# FirstProject.net
KiCad netlist of a schematic drawn in Altium Designer
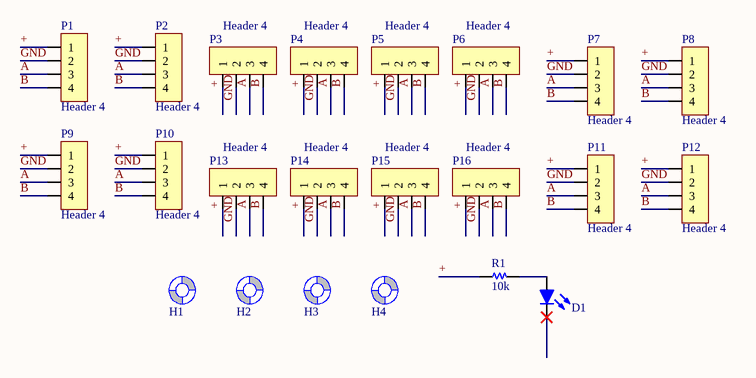
[diagram p0: FirstProject.SchDoc]

(export (version "E")
  (design (tool "Eeschema 10.0.6"))
  (components
    (comp (ref "D1")
      (value "Led")
      (footprint "Led 0603 - red")
      (description "Typical LED")
      (libsource (lib "led") (part "Led"))
    )
    (comp (ref "H1")
      (value "Screw Hole")
      (footprint "SCREW/3.0/6.0")
      (libsource (lib "chipfc_libs") (part "Screw Hole"))
    )
    (comp (ref "H2")
      (value "Screw Hole")
      (footprint "SCREW/3.0/6.0")
      (libsource (lib "chipfc_libs") (part "Screw Hole"))
    )
    (comp (ref "H3")
      (value "Screw Hole")
      (footprint "SCREW/3.0/6.0")
      (libsource (lib "chipfc_libs") (part "Screw Hole"))
    )
    (comp (ref "H4")
      (value "Screw Hole")
      (footprint "SCREW/3.0/6.0")
      (libsource (lib "chipfc_libs") (part "Screw Hole"))
    )
    (comp (ref "P1")
      (value "Header 4")
      (footprint "HDR/Header/4/BOX")
      (description "Header, 4-Pin")
      (libsource (lib "") (part "Header 4_1"))
    )
    (comp (ref "P2")
      (value "Header 4")
      (footprint "HDR/Header/4/BOX")
      (description "Header, 4-Pin")
      (libsource (lib "") (part "Header 4_1"))
    )
    (comp (ref "P3")
      (value "Header 4")
      (footprint "HDR/Terminal/4/RA")
      (description "Header, 4-Pin")
      (libsource (lib "connectors") (part "Header 4"))
    )
    (comp (ref "P4")
      (value "Header 4")
      (footprint "HDR/Terminal/4/RA")
      (description "Header, 4-Pin")
      (libsource (lib "connectors") (part "Header 4"))
    )
    (comp (ref "P5")
      (value "Header 4")
      (footprint "HDR/Terminal/4/RA")
      (description "Header, 4-Pin")
      (libsource (lib "connectors") (part "Header 4"))
    )
    (comp (ref "P6")
      (value "Header 4")
      (footprint "HDR/Terminal/4/RA")
      (description "Header, 4-Pin")
      (libsource (lib "connectors") (part "Header 4"))
    )
    (comp (ref "P7")
      (value "Header 4")
      (footprint "HDR/Header/4/BOX")
      (description "Header, 4-Pin")
      (libsource (lib "") (part "Header 4_1"))
    )
    (comp (ref "P8")
      (value "Header 4")
      (footprint "HDR/Header/4/BOX")
      (description "Header, 4-Pin")
      (libsource (lib "") (part "Header 4_1"))
    )
    (comp (ref "P9")
      (value "Header 4")
      (footprint "HDR/Header/4/BOX")
      (description "Header, 4-Pin")
      (libsource (lib "") (part "Header 4_1"))
    )
    (comp (ref "P10")
      (value "Header 4")
      (footprint "HDR/Header/4/BOX")
      (description "Header, 4-Pin")
      (libsource (lib "") (part "Header 4_1"))
    )
    (comp (ref "P11")
      (value "Header 4")
      (footprint "HDR/Header/4/BOX")
      (description "Header, 4-Pin")
      (libsource (lib "") (part "Header 4_1"))
    )
    (comp (ref "P12")
      (value "Header 4")
      (footprint "HDR/Header/4/BOX")
      (description "Header, 4-Pin")
      (libsource (lib "") (part "Header 4_1"))
    )
    (comp (ref "P13")
      (value "Header 4")
      (footprint "HDR/Terminal/4/RA")
      (description "Header, 4-Pin")
      (libsource (lib "connectors") (part "Header 4"))
    )
    (comp (ref "P14")
      (value "Header 4")
      (footprint "HDR/Terminal/4/RA")
      (description "Header, 4-Pin")
      (libsource (lib "connectors") (part "Header 4"))
    )
    (comp (ref "P15")
      (value "Header 4")
      (footprint "HDR/Terminal/4/RA")
      (description "Header, 4-Pin")
      (libsource (lib "connectors") (part "Header 4"))
    )
    (comp (ref "P16")
      (value "Header 4")
      (footprint "HDR/Terminal/4/RA")
      (description "Header, 4-Pin")
      (libsource (lib "connectors") (part "Header 4"))
    )
    (comp (ref "R1")
      (value "10k")
      (footprint "R 0805")
      (description "Resistor")
      (libsource (lib "chipfc_libs") (part "Resistor"))
    )
  )
  (nets
    (net (code "1") (name "/+") (class "Default")
      (node (ref "P1") (pin "1") (pinfunction "1_1") (pintype "passive"))
      (node (ref "P10") (pin "1") (pinfunction "1_1") (pintype "passive"))
      (node (ref "P11") (pin "1") (pinfunction "1_1") (pintype "passive"))
      (node (ref "P12") (pin "1") (pinfunction "1_1") (pintype "passive"))
      (node (ref "P13") (pin "1") (pinfunction "1_1") (pintype "passive"))
      (node (ref "P14") (pin "1") (pinfunction "1_1") (pintype "passive"))
      (node (ref "P15") (pin "1") (pinfunction "1_1") (pintype "passive"))
      (node (ref "P16") (pin "1") (pinfunction "1_1") (pintype "passive"))
      (node (ref "P2") (pin "1") (pinfunction "1_1") (pintype "passive"))
      (node (ref "P3") (pin "1") (pinfunction "1_1") (pintype "passive"))
      (node (ref "P4") (pin "1") (pinfunction "1_1") (pintype "passive"))
      (node (ref "P5") (pin "1") (pinfunction "1_1") (pintype "passive"))
      (node (ref "P6") (pin "1") (pinfunction "1_1") (pintype "passive"))
      (node (ref "P7") (pin "1") (pinfunction "1_1") (pintype "passive"))
      (node (ref "P8") (pin "1") (pinfunction "1_1") (pintype "passive"))
      (node (ref "P9") (pin "1") (pinfunction "1_1") (pintype "passive"))
      (node (ref "R1") (pin "1") (pinfunction "1_1") (pintype "passive"))
    )
    (net (code "2") (name "/A") (class "Default")
      (node (ref "P1") (pin "3") (pinfunction "3_3") (pintype "passive"))
      (node (ref "P10") (pin "3") (pinfunction "3_3") (pintype "passive"))
      (node (ref "P11") (pin "3") (pinfunction "3_3") (pintype "passive"))
      (node (ref "P12") (pin "3") (pinfunction "3_3") (pintype "passive"))
      (node (ref "P13") (pin "3") (pinfunction "3_3") (pintype "passive"))
      (node (ref "P14") (pin "3") (pinfunction "3_3") (pintype "passive"))
      (node (ref "P15") (pin "3") (pinfunction "3_3") (pintype "passive"))
      (node (ref "P16") (pin "3") (pinfunction "3_3") (pintype "passive"))
      (node (ref "P2") (pin "3") (pinfunction "3_3") (pintype "passive"))
      (node (ref "P3") (pin "3") (pinfunction "3_3") (pintype "passive"))
      (node (ref "P4") (pin "3") (pinfunction "3_3") (pintype "passive"))
      (node (ref "P5") (pin "3") (pinfunction "3_3") (pintype "passive"))
      (node (ref "P6") (pin "3") (pinfunction "3_3") (pintype "passive"))
      (node (ref "P7") (pin "3") (pinfunction "3_3") (pintype "passive"))
      (node (ref "P8") (pin "3") (pinfunction "3_3") (pintype "passive"))
      (node (ref "P9") (pin "3") (pinfunction "3_3") (pintype "passive"))
    )
    (net (code "3") (name "/B") (class "Default")
      (node (ref "P1") (pin "4") (pinfunction "4_4") (pintype "passive"))
      (node (ref "P10") (pin "4") (pinfunction "4_4") (pintype "passive"))
      (node (ref "P11") (pin "4") (pinfunction "4_4") (pintype "passive"))
      (node (ref "P12") (pin "4") (pinfunction "4_4") (pintype "passive"))
      (node (ref "P13") (pin "4") (pinfunction "4_4") (pintype "passive"))
      (node (ref "P14") (pin "4") (pinfunction "4_4") (pintype "passive"))
      (node (ref "P15") (pin "4") (pinfunction "4_4") (pintype "passive"))
      (node (ref "P16") (pin "4") (pinfunction "4_4") (pintype "passive"))
      (node (ref "P2") (pin "4") (pinfunction "4_4") (pintype "passive"))
      (node (ref "P3") (pin "4") (pinfunction "4_4") (pintype "passive"))
      (node (ref "P4") (pin "4") (pinfunction "4_4") (pintype "passive"))
      (node (ref "P5") (pin "4") (pinfunction "4_4") (pintype "passive"))
      (node (ref "P6") (pin "4") (pinfunction "4_4") (pintype "passive"))
      (node (ref "P7") (pin "4") (pinfunction "4_4") (pintype "passive"))
      (node (ref "P8") (pin "4") (pinfunction "4_4") (pintype "passive"))
      (node (ref "P9") (pin "4") (pinfunction "4_4") (pintype "passive"))
    )
    (net (code "4") (name "/GND") (class "Default")
      (node (ref "P1") (pin "2") (pinfunction "2_2") (pintype "passive"))
      (node (ref "P10") (pin "2") (pinfunction "2_2") (pintype "passive"))
      (node (ref "P11") (pin "2") (pinfunction "2_2") (pintype "passive"))
      (node (ref "P12") (pin "2") (pinfunction "2_2") (pintype "passive"))
      (node (ref "P13") (pin "2") (pinfunction "2_2") (pintype "passive"))
      (node (ref "P14") (pin "2") (pinfunction "2_2") (pintype "passive"))
      (node (ref "P15") (pin "2") (pinfunction "2_2") (pintype "passive"))
      (node (ref "P16") (pin "2") (pinfunction "2_2") (pintype "passive"))
      (node (ref "P2") (pin "2") (pinfunction "2_2") (pintype "passive"))
      (node (ref "P3") (pin "2") (pinfunction "2_2") (pintype "passive"))
      (node (ref "P4") (pin "2") (pinfunction "2_2") (pintype "passive"))
      (node (ref "P5") (pin "2") (pinfunction "2_2") (pintype "passive"))
      (node (ref "P6") (pin "2") (pinfunction "2_2") (pintype "passive"))
      (node (ref "P7") (pin "2") (pinfunction "2_2") (pintype "passive"))
      (node (ref "P8") (pin "2") (pinfunction "2_2") (pintype "passive"))
      (node (ref "P9") (pin "2") (pinfunction "2_2") (pintype "passive"))
    )
    (net (code "5") (name "Net-(D1-A)") (class "Default")
      (node (ref "D1") (pin "1") (pinfunction "A_1") (pintype "passive"))
      (node (ref "R1") (pin "2") (pinfunction "2_2") (pintype "passive"))
    )
    (net (code "6") (name "unconnected-(D1-K-Pad2)") (class "Default")
      (node (ref "D1") (pin "2") (pinfunction "K_2") (pintype "passive+no_connect"))
    )
    (net (code "7") (name "unconnected-(H1-Screw-Pad1)") (class "Default")
      (node (ref "H1") (pin "1") (pinfunction "Screw_1") (pintype "passive"))
    )
    (net (code "8") (name "unconnected-(H2-Screw-Pad1)") (class "Default")
      (node (ref "H2") (pin "1") (pinfunction "Screw_1") (pintype "passive"))
    )
    (net (code "9") (name "unconnected-(H3-Screw-Pad1)") (class "Default")
      (node (ref "H3") (pin "1") (pinfunction "Screw_1") (pintype "passive"))
    )
    (net (code "10") (name "unconnected-(H4-Screw-Pad1)") (class "Default")
      (node (ref "H4") (pin "1") (pinfunction "Screw_1") (pintype "passive"))
    )
  )
)
